# PAGE3_-_POWER.net
KiCad netlist of a schematic drawn in Altium Designer
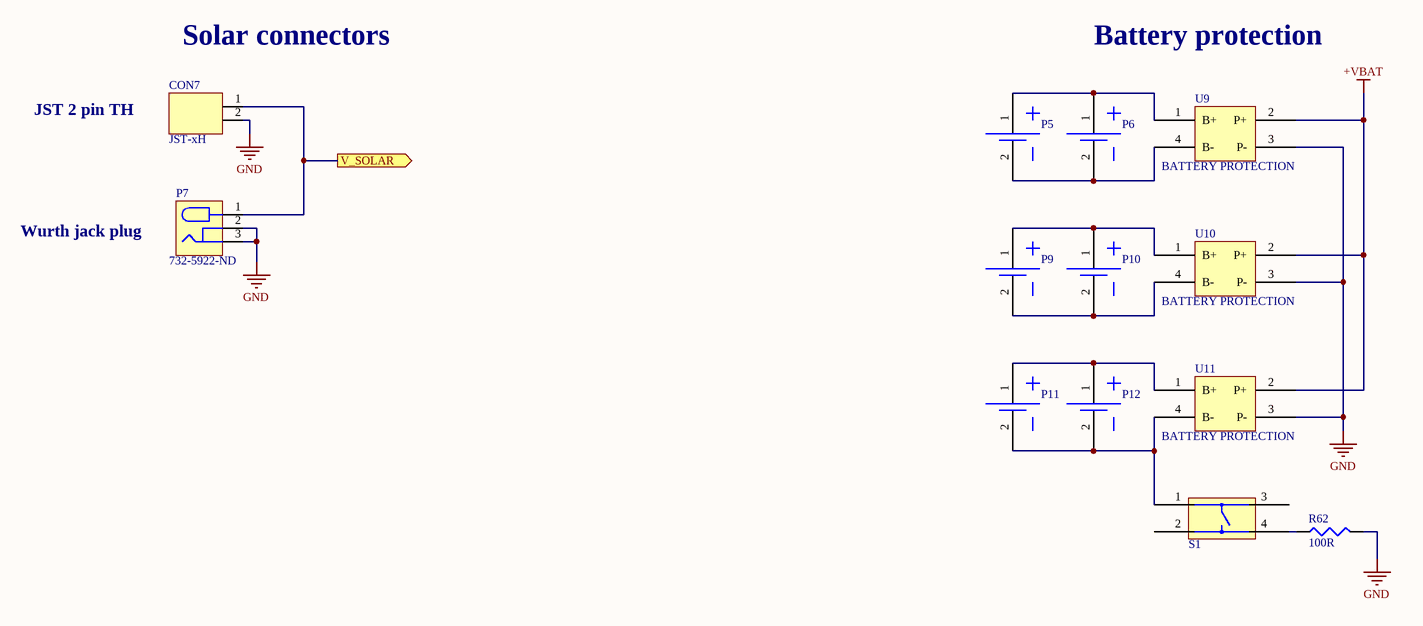
[diagram p0: PAGE3 - POWER.SchDoc]

(export (version "E")
  (design (tool "Eeschema 10.0.6"))
  (components
    (comp (ref "CON7")
      (value "JST-xH")
      (footprint "JST_2PIN_TH")
      (description "Wire-To-Board Connector, Vertical, 2.5 mm, 2 Contacts, Header, XH Series, Through Hole, 1 Rows")
      (libsource (lib "Connectors") (part "B2B-XH-A (LF)(SN)"))
    )
    (comp (ref "P5")
      (value "BAT - 18650")
      (footprint "BATTERY HOLDER 18650")
      (description "BATERRY HOLDER 18650")
      (libsource (lib "Mechanical") (part "BAT - 18650"))
    )
    (comp (ref "P6")
      (value "BAT - 18650")
      (footprint "BATTERY HOLDER 18650")
      (description "BATERRY HOLDER 18650")
      (libsource (lib "Mechanical") (part "BAT - 18650"))
    )
    (comp (ref "P7")
      (value "732-5922-ND")
      (footprint "732-5922-ND")
      (description "Power Barrel Connector Jack 1.05mm ID (0.041\"), 3.50mm OD (0.138\") Through Hole, Right Angle")
      (libsource (lib "Connectors") (part "CONN PWR JACK 1.05X3.5MM"))
    )
    (comp (ref "P9")
      (value "BAT - 18650")
      (footprint "BATTERY HOLDER 18650")
      (description "BATERRY HOLDER 18650")
      (libsource (lib "Mechanical") (part "BAT - 18650"))
    )
    (comp (ref "P10")
      (value "BAT - 18650")
      (footprint "BATTERY HOLDER 18650")
      (description "BATERRY HOLDER 18650")
      (libsource (lib "Mechanical") (part "BAT - 18650"))
    )
    (comp (ref "P11")
      (value "BAT - 18650")
      (footprint "BATTERY HOLDER 18650")
      (description "BATERRY HOLDER 18650")
      (libsource (lib "Mechanical") (part "BAT - 18650"))
    )
    (comp (ref "P12")
      (value "BAT - 18650")
      (footprint "BATTERY HOLDER 18650")
      (description "BATERRY HOLDER 18650")
      (libsource (lib "Mechanical") (part "BAT - 18650"))
    )
    (comp (ref "R62")
      (value "100R")
      (footprint "RES0603")
      (description "MULTICOMP - MC0063W06031100R - RES, THICK FILM, 100R, 1%, 0.063W, 0603")
      (fields
        (field (name "MANUFACTURER") "MULTICOMP")
        (field (name "MANUFACTURER PART NUMBER") "MC0063W06031100R")
      )
      (libsource (lib "Passive") (part "R - 100R"))
    )
    (comp (ref "S1")
      (value "BTN - KMR221NGLFS")
      (footprint "SW")
      (description "SWITCH TACTILE SPST-NO 0.05A 32V")
      (fields (field (name "MANUFACTURER") "ITT C&K") (field (name "MANUFACTURER PART NUMBER") "KMR221NGLFS"))
      (libsource (lib "Mechanical") (part "BTN - KMR221NGLFS"))
    )
    (comp (ref "U9")
      (value "BATTERY PROTECTION")
      (footprint "BATTERY PROTECTION")
      (libsource (lib "Mechanical") (part "BATTERY PROTECTION"))
    )
    (comp (ref "U10")
      (value "BATTERY PROTECTION")
      (footprint "BATTERY PROTECTION")
      (libsource (lib "Mechanical") (part "BATTERY PROTECTION"))
    )
    (comp (ref "U11")
      (value "BATTERY PROTECTION")
      (footprint "BATTERY PROTECTION")
      (libsource (lib "Mechanical") (part "BATTERY PROTECTION"))
    )
  )
  (nets
    (net (code "1") (name "+VBAT") (class "Default")
      (node (ref "U10") (pin "2") (pinfunction "P+_2") (pintype "passive"))
      (node (ref "U11") (pin "2") (pinfunction "P+_2") (pintype "passive"))
      (node (ref "U9") (pin "2") (pinfunction "P+_2") (pintype "passive"))
    )
    (net (code "2") (name "/V_SOLAR") (class "Default")
      (node (ref "CON7") (pin "1") (pinfunction "1_1") (pintype "passive"))
      (node (ref "P7") (pin "1") (pinfunction "1_1") (pintype "passive"))
    )
    (net (code "3") (name "GND") (class "Default")
      (node (ref "CON7") (pin "2") (pinfunction "2_2") (pintype "passive"))
      (node (ref "P7") (pin "2") (pinfunction "2_2") (pintype "passive"))
      (node (ref "P7") (pin "3") (pinfunction "3_3") (pintype "passive"))
      (node (ref "R62") (pin "2") (pinfunction "2_2") (pintype "passive"))
      (node (ref "U10") (pin "3") (pinfunction "P-_3") (pintype "passive"))
      (node (ref "U11") (pin "3") (pinfunction "P-_3") (pintype "passive"))
      (node (ref "U9") (pin "3") (pinfunction "P-_3") (pintype "passive"))
    )
    (net (code "4") (name "Net-(R62-Pad1)") (class "Default")
      (node (ref "R62") (pin "1") (pinfunction "1_1") (pintype "passive"))
      (node (ref "S1") (pin "4") (pinfunction "4_4") (pintype "passive"))
    )
    (net (code "5") (name "Net-(U9-B+)") (class "Default")
      (node (ref "P5") (pin "1") (pintype "passive"))
      (node (ref "P6") (pin "1") (pintype "passive"))
      (node (ref "U9") (pin "1") (pinfunction "B+_1") (pintype "passive"))
    )
    (net (code "6") (name "Net-(U9-B-)") (class "Default")
      (node (ref "P5") (pin "2") (pintype "passive"))
      (node (ref "P6") (pin "2") (pintype "passive"))
      (node (ref "U9") (pin "4") (pinfunction "B-_4") (pintype "passive"))
    )
    (net (code "7") (name "Net-(U10-B+)") (class "Default")
      (node (ref "P10") (pin "1") (pintype "passive"))
      (node (ref "P9") (pin "1") (pintype "passive"))
      (node (ref "U10") (pin "1") (pinfunction "B+_1") (pintype "passive"))
    )
    (net (code "8") (name "Net-(U10-B-)") (class "Default")
      (node (ref "P10") (pin "2") (pintype "passive"))
      (node (ref "P9") (pin "2") (pintype "passive"))
      (node (ref "U10") (pin "4") (pinfunction "B-_4") (pintype "passive"))
    )
    (net (code "9") (name "Net-(U11-B+)") (class "Default")
      (node (ref "P11") (pin "1") (pintype "passive"))
      (node (ref "P12") (pin "1") (pintype "passive"))
      (node (ref "U11") (pin "1") (pinfunction "B+_1") (pintype "passive"))
    )
    (net (code "10") (name "Net-(U11-B-)") (class "Default")
      (node (ref "P11") (pin "2") (pintype "passive"))
      (node (ref "P12") (pin "2") (pintype "passive"))
      (node (ref "S1") (pin "1") (pinfunction "1_1") (pintype "passive"))
      (node (ref "U11") (pin "4") (pinfunction "B-_4") (pintype "passive"))
    )
    (net (code "11") (name "unconnected-(S1-Pad2)") (class "Default")
      (node (ref "S1") (pin "2") (pinfunction "2_2") (pintype "passive"))
    )
    (net (code "12") (name "unconnected-(S1-Pad3)") (class "Default")
      (node (ref "S1") (pin "3") (pinfunction "3_3") (pintype "passive"))
    )
  )
)
